# GoPro-Pilot.net
KiCad netlist of a schematic drawn in EAGLE
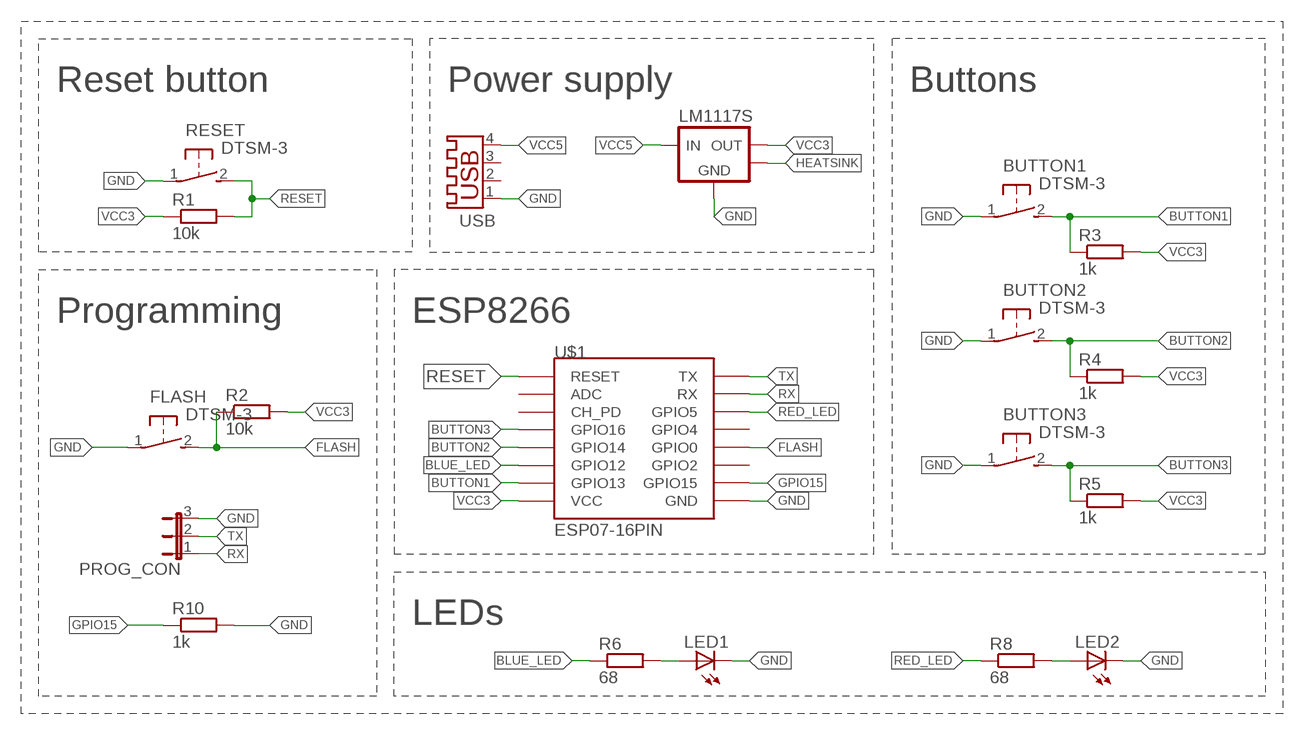
[diagram p0: schematic, sheet 1]

(export (version "E")
  (design (tool "Eeschema 10.0.6"))
  (components
    (comp (ref "BUTTON1")
      (value "DTSM-3")
      (footprint "eagle-import:DTSM-3")
      (libsource (lib "eagle-import") (part "DTSM-3"))
    )
    (comp (ref "BUTTON2")
      (value "DTSM-3")
      (footprint "eagle-import:DTSM-3")
      (libsource (lib "eagle-import") (part "DTSM-3"))
    )
    (comp (ref "BUTTON3")
      (value "DTSM-3")
      (footprint "eagle-import:DTSM-3")
      (libsource (lib "eagle-import") (part "DTSM-3"))
    )
    (comp (ref "FLASH")
      (value "DTSM-3")
      (footprint "eagle-import:DTSM-3")
      (libsource (lib "eagle-import") (part "DTSM-3"))
    )
    (comp (ref "LED1")
      (value "LEDSML0805")
      (footprint "eagle-import:SML0805")
      (libsource (lib "eagle-import") (part "LEDSML0805"))
    )
    (comp (ref "LED2")
      (value "LEDSML0805")
      (footprint "eagle-import:SML0805")
      (libsource (lib "eagle-import") (part "LEDSML0805"))
    )
    (comp (ref "LM1117S")
      (value "LM1117-SOT223")
      (footprint "eagle-import:SOT-223-3")
      (libsource (lib "eagle-import") (part "LM1117-SOT223"))
    )
    (comp (ref "PROG_CON")
      (value "JP2E")
      (footprint "eagle-import:JP2")
      (libsource (lib "eagle-import") (part "JP2E"))
    )
    (comp (ref "R1")
      (value "10k")
      (footprint "eagle-import:R1005")
      (libsource (lib "eagle-import") (part "RR1005"))
    )
    (comp (ref "R2")
      (value "10k")
      (footprint "eagle-import:R1005")
      (libsource (lib "eagle-import") (part "RR1005"))
    )
    (comp (ref "R3")
      (value "1k")
      (footprint "eagle-import:R1005")
      (libsource (lib "eagle-import") (part "RR1005"))
    )
    (comp (ref "R4")
      (value "1k")
      (footprint "eagle-import:R1005")
      (libsource (lib "eagle-import") (part "RR1005"))
    )
    (comp (ref "R5")
      (value "1k")
      (footprint "eagle-import:R1005")
      (libsource (lib "eagle-import") (part "RR1005"))
    )
    (comp (ref "R6")
      (value "68")
      (footprint "eagle-import:R1005")
      (libsource (lib "eagle-import") (part "RR1005"))
    )
    (comp (ref "R8")
      (value "68")
      (footprint "eagle-import:R1005")
      (libsource (lib "eagle-import") (part "RR1005"))
    )
    (comp (ref "R10")
      (value "1k")
      (footprint "eagle-import:R1005")
      (libsource (lib "eagle-import") (part "RR1005"))
    )
    (comp (ref "RESET")
      (value "DTSM-3")
      (footprint "eagle-import:DTSM-3")
      (libsource (lib "eagle-import") (part "DTSM-3"))
    )
    (comp (ref "U$1")
      (value "ESP07-16PIN")
      (footprint "eagle-import:ESP07-16PIN")
      (libsource (lib "eagle-import") (part "ESP07-16PIN"))
    )
    (comp (ref "USB")
      (value "USB-A003")
      (footprint "eagle-import:USB-A003")
      (libsource (lib "eagle-import") (part "USB-A003"))
    )
  )
  (nets
    (net (code "1") (name "BLUE_LED") (class "Default")
      (node (ref "R6") (pin "1") (pinfunction "1_1") (pintype "passive"))
      (node (ref "U$1") (pin "GPIO12") (pinfunction "GPIO12_GPIO12") (pintype "bidirectional"))
    )
    (net (code "2") (name "BUTTON1") (class "Default")
      (node (ref "BUTTON1") (pin "2") (pinfunction "2_2") (pintype "passive"))
      (node (ref "R3") (pin "1") (pinfunction "1_1") (pintype "passive"))
      (node (ref "U$1") (pin "GPIO13") (pinfunction "GPIO13_GPIO13") (pintype "bidirectional"))
    )
    (net (code "3") (name "BUTTON2") (class "Default")
      (node (ref "BUTTON2") (pin "2") (pinfunction "2_2") (pintype "passive"))
      (node (ref "R4") (pin "1") (pinfunction "1_1") (pintype "passive"))
      (node (ref "U$1") (pin "GPIO14") (pinfunction "GPIO14_GPIO14") (pintype "bidirectional"))
    )
    (net (code "4") (name "BUTTON3") (class "Default")
      (node (ref "BUTTON3") (pin "2") (pinfunction "2_2") (pintype "passive"))
      (node (ref "R5") (pin "1") (pinfunction "1_1") (pintype "passive"))
      (node (ref "U$1") (pin "GPIO16") (pinfunction "GPIO16_GPIO16") (pintype "bidirectional"))
    )
    (net (code "5") (name "FLASH") (class "Default")
      (node (ref "FLASH") (pin "2") (pinfunction "2_2") (pintype "passive"))
      (node (ref "R2") (pin "1") (pinfunction "1_1") (pintype "passive"))
      (node (ref "U$1") (pin "GPIO0") (pinfunction "GPIO0_GPIO0") (pintype "bidirectional"))
    )
    (net (code "6") (name "GND") (class "Default")
      (node (ref "BUTTON1") (pin "1") (pinfunction "1_1") (pintype "passive"))
      (node (ref "BUTTON2") (pin "1") (pinfunction "1_1") (pintype "passive"))
      (node (ref "BUTTON3") (pin "1") (pinfunction "1_1") (pintype "passive"))
      (node (ref "FLASH") (pin "1") (pinfunction "1_1") (pintype "passive"))
      (node (ref "LED1") (pin "C") (pinfunction "C_C") (pintype "passive"))
      (node (ref "LED2") (pin "C") (pinfunction "C_C") (pintype "passive"))
      (node (ref "LM1117S") (pin "1") (pinfunction "GND_1") (pintype "power_in"))
      (node (ref "PROG_CON") (pin "3") (pinfunction "3_3") (pintype "passive"))
      (node (ref "R10") (pin "2") (pinfunction "2_2") (pintype "passive"))
      (node (ref "RESET") (pin "1") (pinfunction "1_1") (pintype "passive"))
      (node (ref "U$1") (pin "GND") (pinfunction "GND_GND") (pintype "bidirectional"))
      (node (ref "USB") (pin "1") (pinfunction "1_1") (pintype "passive"))
    )
    (net (code "7") (name "GPIO15") (class "Default")
      (node (ref "R10") (pin "1") (pinfunction "1_1") (pintype "passive"))
      (node (ref "U$1") (pin "GPIO15") (pinfunction "GPIO15_GPIO15") (pintype "bidirectional"))
    )
    (net (code "8") (name "HEATSINK") (class "Default")
      (node (ref "LM1117S") (pin "4") (pinfunction "HEATSINK_4") (pintype "power_in"))
    )
    (net (code "9") (name "Net-(LED1-PadA)") (class "Default")
      (node (ref "LED1") (pin "A") (pinfunction "A_A") (pintype "passive"))
      (node (ref "R6") (pin "2") (pinfunction "2_2") (pintype "passive"))
    )
    (net (code "10") (name "Net-(LED2-PadA)") (class "Default")
      (node (ref "LED2") (pin "A") (pinfunction "A_A") (pintype "passive"))
      (node (ref "R8") (pin "2") (pinfunction "2_2") (pintype "passive"))
    )
    (net (code "11") (name "RED_LED") (class "Default")
      (node (ref "R8") (pin "1") (pinfunction "1_1") (pintype "passive"))
      (node (ref "U$1") (pin "GPIO4") (pinfunction "GPIO5_GPIO4") (pintype "bidirectional"))
    )
    (net (code "12") (name "RESET") (class "Default")
      (node (ref "R1") (pin "2") (pinfunction "2_2") (pintype "passive"))
      (node (ref "RESET") (pin "2") (pinfunction "2_2") (pintype "passive"))
      (node (ref "U$1") (pin "REST") (pinfunction "RESET_REST") (pintype "bidirectional"))
    )
    (net (code "13") (name "RX") (class "Default")
      (node (ref "PROG_CON") (pin "1") (pinfunction "1_1") (pintype "passive"))
      (node (ref "U$1") (pin "RX") (pinfunction "RX_RX") (pintype "bidirectional"))
    )
    (net (code "14") (name "TX") (class "Default")
      (node (ref "PROG_CON") (pin "2") (pinfunction "2_2") (pintype "passive"))
      (node (ref "U$1") (pin "TX") (pinfunction "TX_TX") (pintype "bidirectional"))
    )
    (net (code "15") (name "VCC3") (class "Default")
      (node (ref "LM1117S") (pin "2") (pinfunction "VOUT_2") (pintype "power_in"))
      (node (ref "R1") (pin "1") (pinfunction "1_1") (pintype "passive"))
      (node (ref "R2") (pin "2") (pinfunction "2_2") (pintype "passive"))
      (node (ref "R3") (pin "2") (pinfunction "2_2") (pintype "passive"))
      (node (ref "R4") (pin "2") (pinfunction "2_2") (pintype "passive"))
      (node (ref "R5") (pin "2") (pinfunction "2_2") (pintype "passive"))
      (node (ref "U$1") (pin "VCC") (pinfunction "VCC_VCC") (pintype "bidirectional"))
    )
    (net (code "16") (name "VCC5") (class "Default")
      (node (ref "LM1117S") (pin "3") (pinfunction "VIN_3") (pintype "power_in"))
      (node (ref "USB") (pin "4") (pinfunction "4_4") (pintype "passive"))
    )
    (net (code "17") (name "unconnected-(U$1-GPIO4-PadGPIO5)") (class "Default")
      (node (ref "U$1") (pin "GPIO5") (pinfunction "GPIO4_GPIO5") (pintype "bidirectional"))
    )
    (net (code "18") (name "unconnected-(U$1-PadADC)") (class "Default")
      (node (ref "U$1") (pin "ADC") (pinfunction "ADC_ADC") (pintype "bidirectional"))
    )
    (net (code "19") (name "unconnected-(U$1-PadCH_PD)") (class "Default")
      (node (ref "U$1") (pin "CH_PD") (pinfunction "CH_PD_CH_PD") (pintype "bidirectional"))
    )
    (net (code "20") (name "unconnected-(U$1-PadGPIO2)") (class "Default")
      (node (ref "U$1") (pin "GPIO2") (pinfunction "GPIO2_GPIO2") (pintype "bidirectional"))
    )
    (net (code "21") (name "unconnected-(USB-Pad2)") (class "Default")
      (node (ref "USB") (pin "2") (pinfunction "2_2") (pintype "passive"))
    )
    (net (code "22") (name "unconnected-(USB-Pad3)") (class "Default")
      (node (ref "USB") (pin "3") (pinfunction "3_3") (pintype "passive"))
    )
  )
)
